# Input_Stage.net
KiCad netlist of a schematic drawn in Altium Designer
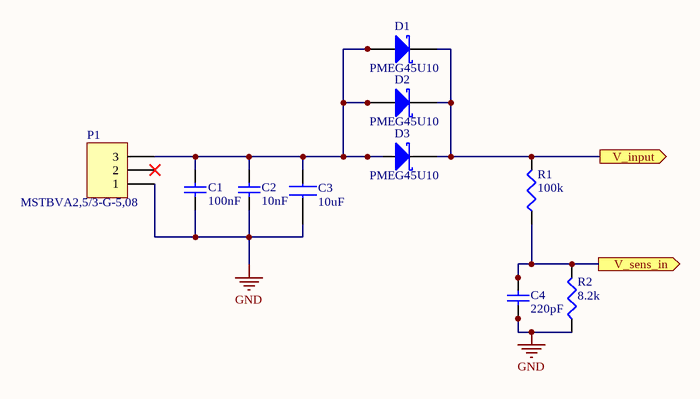
[diagram p0: Input_Stage.SchDoc]

(export (version "E")
  (design (tool "Eeschema 10.0.6"))
  (components
    (comp (ref "C1")
      (value "100nF")
      (footprint "CAPC3216X180N")
      (description "Capacitor 100nF")
      (fields (field (name "Comment") "10nF") (field (name "PUBLISHER") "Altium Limited"))
      (libsource (lib "Sch_Capacitors") (part "CC1206KKX7R0BB104"))
    )
    (comp (ref "C2")
      (value "10nF")
      (footprint "CAPC3216X180N")
      (description "Capacitor 10nF")
      (fields (field (name "Comment") "100µF") (field (name "PUBLISHER") "Altium Limited"))
      (libsource (lib "Sch_Capacitors") (part "C1206C103K1RACTU"))
    )
    (comp (ref "C3")
      (value "10uF")
      (footprint "CAPC3225X270N")
      (description "Ceramic capacitor 10uF")
      (fields
        (field (name "MANUFACTURER_PART_NUMBER") "GRM32EC72A106KE05K")
        (field (name "MOUSER PART NUMBER") "81-GRM32EC72A106KE5K")
      )
      (libsource (lib "Sch_Capacitors") (part "GRM32EC72A106KE05K"))
    )
    (comp (ref "C4")
      (value "220pF")
      (footprint "PcbLib1:CAPC3216X180N")
      (description "Capacitor 220pF")
      (fields (field (name "PUBLISHER") "Altium Limited"))
      (libsource (lib "Sch_Capacitors") (part "VJ1206A221JXBCW1BC"))
    )
    (comp (ref "D1")
      (value "PMEG45U10")
      (footprint "PMEG45U10EPDZ")
      (description "Schottky Diode")
      (fields
        (field (name "MANUFACTURER_PART_NUMBER") "PMEG45U10EPDZ")
        (field (name "MOUSER PART NUMBER") "771-PMEG45U10EPDZ")
      )
      (libsource (lib "Sch_Diodes") (part "PMEG45U10EPDZ"))
    )
    (comp (ref "D2")
      (value "PMEG45U10")
      (footprint "PMEG45U10EPDZ")
      (description "Schottky Diode")
      (fields
        (field (name "MANUFACTURER_PART_NUMBER") "PMEG45U10EPDZ")
        (field (name "MOUSER PART NUMBER") "771-PMEG45U10EPDZ")
      )
      (libsource (lib "Sch_Diodes") (part "PMEG45U10EPDZ"))
    )
    (comp (ref "D3")
      (value "PMEG45U10")
      (footprint "PMEG45U10EPDZ")
      (description "Schottky Diode")
      (fields
        (field (name "MANUFACTURER_PART_NUMBER") "PMEG45U10EPDZ")
        (field (name "MOUSER PART NUMBER") "771-PMEG45U10EPDZ")
      )
      (libsource (lib "Sch_Diodes") (part "PMEG45U10EPDZ"))
    )
    (comp (ref "P1")
      (value "MSTBVA2,5/3-G-5,08")
      (footprint "HDR1X3")
      (description "Header, 3-Pin")
      (fields (field (name "PUBLISHER") "Altium Limited"))
      (libsource (lib "Sch_Headers") (part "MSTBVA2,5/3-G-5,08"))
    )
    (comp (ref "R1")
      (value "100k")
      (footprint "RESC3216X75N")
      (description "Resistor 100k")
      (fields (field (name "Comment") "100KΩ") (field (name "PUBLISHER") "Altium Limited"))
      (libsource (lib "Sch_Resistors") (part "MCWR12X1003FTL"))
    )
    (comp (ref "R2")
      (value "8.2k")
      (footprint "RESC3216X75N")
      (description "Resistor 8.2k")
      (fields (field (name "Comment") "8.2KΩ") (field (name "PUBLISHER") "Altium Limited"))
      (libsource (lib "Sch_Resistors") (part "CRGCQ1206F8K2"))
    )
  )
  (nets
    (net (code "1") (name "/V_input") (class "Default")
      (node (ref "D1") (pin "3") (pinfunction "3_3") (pintype "passive"))
      (node (ref "D2") (pin "3") (pinfunction "3_3") (pintype "passive"))
      (node (ref "D3") (pin "3") (pinfunction "3_3") (pintype "passive"))
      (node (ref "R1") (pin "2") (pinfunction "2_2") (pintype "passive"))
    )
    (net (code "2") (name "/V_sens_in") (class "Default")
      (node (ref "C4") (pin "2") (pinfunction "2_2") (pintype "passive"))
      (node (ref "R1") (pin "1") (pinfunction "1_1") (pintype "passive"))
      (node (ref "R2") (pin "2") (pinfunction "2_2") (pintype "passive"))
    )
    (net (code "3") (name "GND") (class "Default")
      (node (ref "C1") (pin "1") (pinfunction "1_1") (pintype "passive"))
      (node (ref "C2") (pin "1") (pinfunction "1_1") (pintype "passive"))
      (node (ref "C3") (pin "1") (pinfunction "1_1") (pintype "passive"))
      (node (ref "C4") (pin "1") (pinfunction "1_1") (pintype "passive"))
      (node (ref "P1") (pin "1") (pinfunction "1_1") (pintype "passive"))
      (node (ref "R2") (pin "1") (pinfunction "1_1") (pintype "passive"))
    )
    (net (code "4") (name "Net-(C1-Pad2)") (class "Default")
      (node (ref "C1") (pin "2") (pinfunction "2_2") (pintype "passive"))
      (node (ref "C2") (pin "2") (pinfunction "2_2") (pintype "passive"))
      (node (ref "C3") (pin "2") (pinfunction "2_2") (pintype "passive"))
      (node (ref "D1") (pin "1") (pinfunction "1_1") (pintype "passive"))
      (node (ref "D1") (pin "2") (pinfunction "2_2") (pintype "passive"))
      (node (ref "D2") (pin "1") (pinfunction "1_1") (pintype "passive"))
      (node (ref "D2") (pin "2") (pinfunction "2_2") (pintype "passive"))
      (node (ref "D3") (pin "1") (pinfunction "1_1") (pintype "passive"))
      (node (ref "D3") (pin "2") (pinfunction "2_2") (pintype "passive"))
      (node (ref "P1") (pin "3") (pinfunction "3_3") (pintype "passive"))
    )
    (net (code "5") (name "unconnected-(P1-Pad2)") (class "Default")
      (node (ref "P1") (pin "2") (pinfunction "2_2") (pintype "passive+no_connect"))
    )
  )
)
